# Medusa-AI-battery.net
KiCad netlist of a schematic drawn in Altium Designer
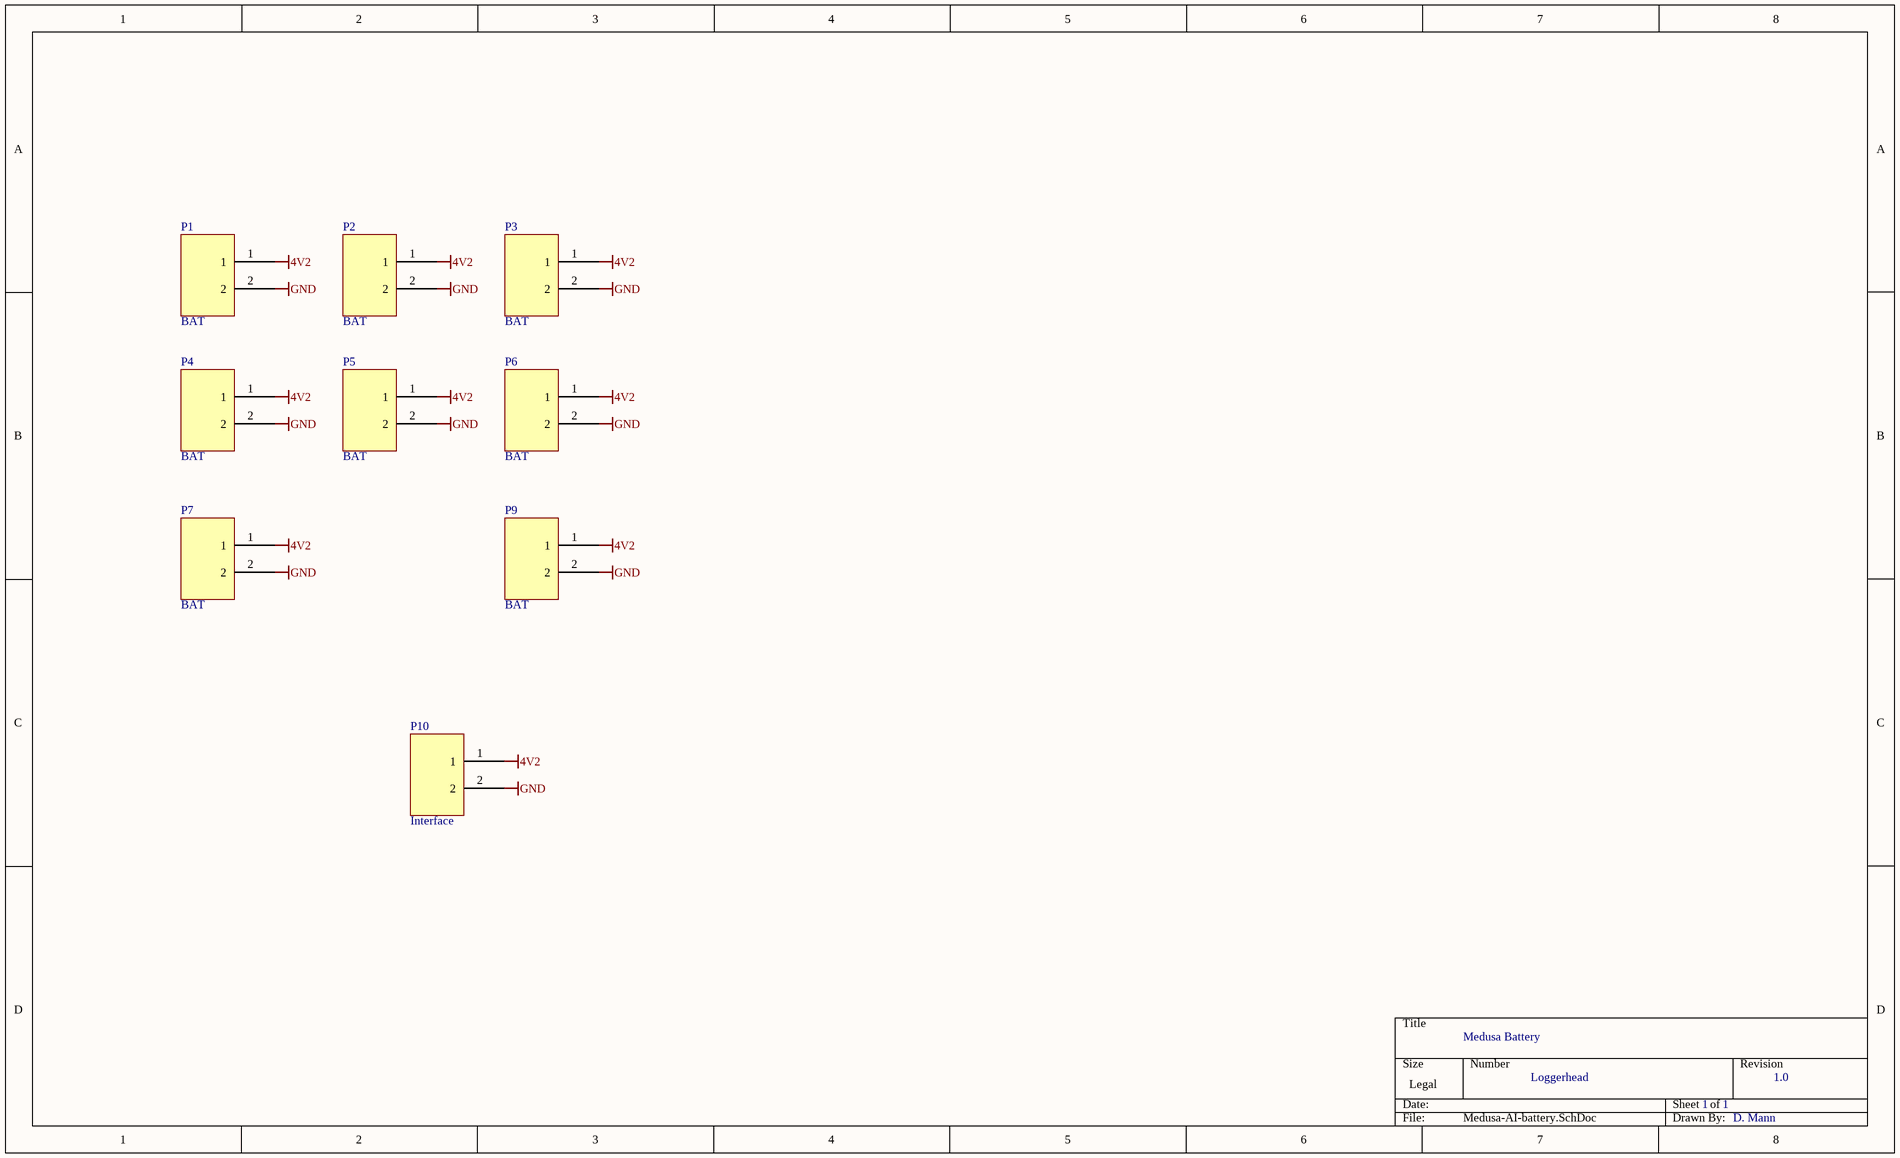
[diagram p0: Medusa-AI-battery.SchDoc]

(export (version "E")
  (design (tool "Eeschema 10.0.6"))
  (components
    (comp (ref "P1")
      (value "BAT")
      (footprint "HDR_2x1_2mm")
      (libsource (lib "Loggerhead") (part "HDR_2x1_2mm"))
    )
    (comp (ref "P2")
      (value "BAT")
      (footprint "HDR_2x1_2mm")
      (libsource (lib "Loggerhead") (part "HDR_2x1_2mm"))
    )
    (comp (ref "P3")
      (value "BAT")
      (footprint "HDR_2x1_2mm")
      (libsource (lib "Loggerhead") (part "HDR_2x1_2mm"))
    )
    (comp (ref "P4")
      (value "BAT")
      (footprint "HDR_2x1_2mm")
      (libsource (lib "Loggerhead") (part "HDR_2x1_2mm"))
    )
    (comp (ref "P5")
      (value "BAT")
      (footprint "HDR_2x1_2mm")
      (libsource (lib "Loggerhead") (part "HDR_2x1_2mm"))
    )
    (comp (ref "P6")
      (value "BAT")
      (footprint "HDR_2x1_2mm")
      (libsource (lib "Loggerhead") (part "HDR_2x1_2mm"))
    )
    (comp (ref "P7")
      (value "BAT")
      (footprint "HDR_2x1_2mm")
      (libsource (lib "Loggerhead") (part "HDR_2x1_2mm"))
    )
    (comp (ref "P9")
      (value "BAT")
      (footprint "HDR_2x1_2mm")
      (libsource (lib "Loggerhead") (part "HDR_2x1_2mm"))
    )
    (comp (ref "P10")
      (value "Interface")
      (footprint "HDR_2x1_2mm")
      (libsource (lib "Loggerhead") (part "HDR_2x1_2mm"))
    )
  )
  (nets
    (net (code "1") (name "4V2") (class "Default")
      (node (ref "P1") (pin "1") (pinfunction "1_1") (pintype "passive"))
      (node (ref "P10") (pin "1") (pinfunction "1_1") (pintype "passive"))
      (node (ref "P2") (pin "1") (pinfunction "1_1") (pintype "passive"))
      (node (ref "P3") (pin "1") (pinfunction "1_1") (pintype "passive"))
      (node (ref "P4") (pin "1") (pinfunction "1_1") (pintype "passive"))
      (node (ref "P5") (pin "1") (pinfunction "1_1") (pintype "passive"))
      (node (ref "P6") (pin "1") (pinfunction "1_1") (pintype "passive"))
      (node (ref "P7") (pin "1") (pinfunction "1_1") (pintype "passive"))
      (node (ref "P9") (pin "1") (pinfunction "1_1") (pintype "passive"))
    )
    (net (code "2") (name "GND") (class "Default")
      (node (ref "P1") (pin "2") (pinfunction "2_2") (pintype "passive"))
      (node (ref "P10") (pin "2") (pinfunction "2_2") (pintype "passive"))
      (node (ref "P2") (pin "2") (pinfunction "2_2") (pintype "passive"))
      (node (ref "P3") (pin "2") (pinfunction "2_2") (pintype "passive"))
      (node (ref "P4") (pin "2") (pinfunction "2_2") (pintype "passive"))
      (node (ref "P5") (pin "2") (pinfunction "2_2") (pintype "passive"))
      (node (ref "P6") (pin "2") (pinfunction "2_2") (pintype "passive"))
      (node (ref "P7") (pin "2") (pinfunction "2_2") (pintype "passive"))
      (node (ref "P9") (pin "2") (pinfunction "2_2") (pintype "passive"))
    )
  )
)
